# m_ch_ho_n_ch_nh.net
KiCad netlist of a schematic drawn in Altium Designer
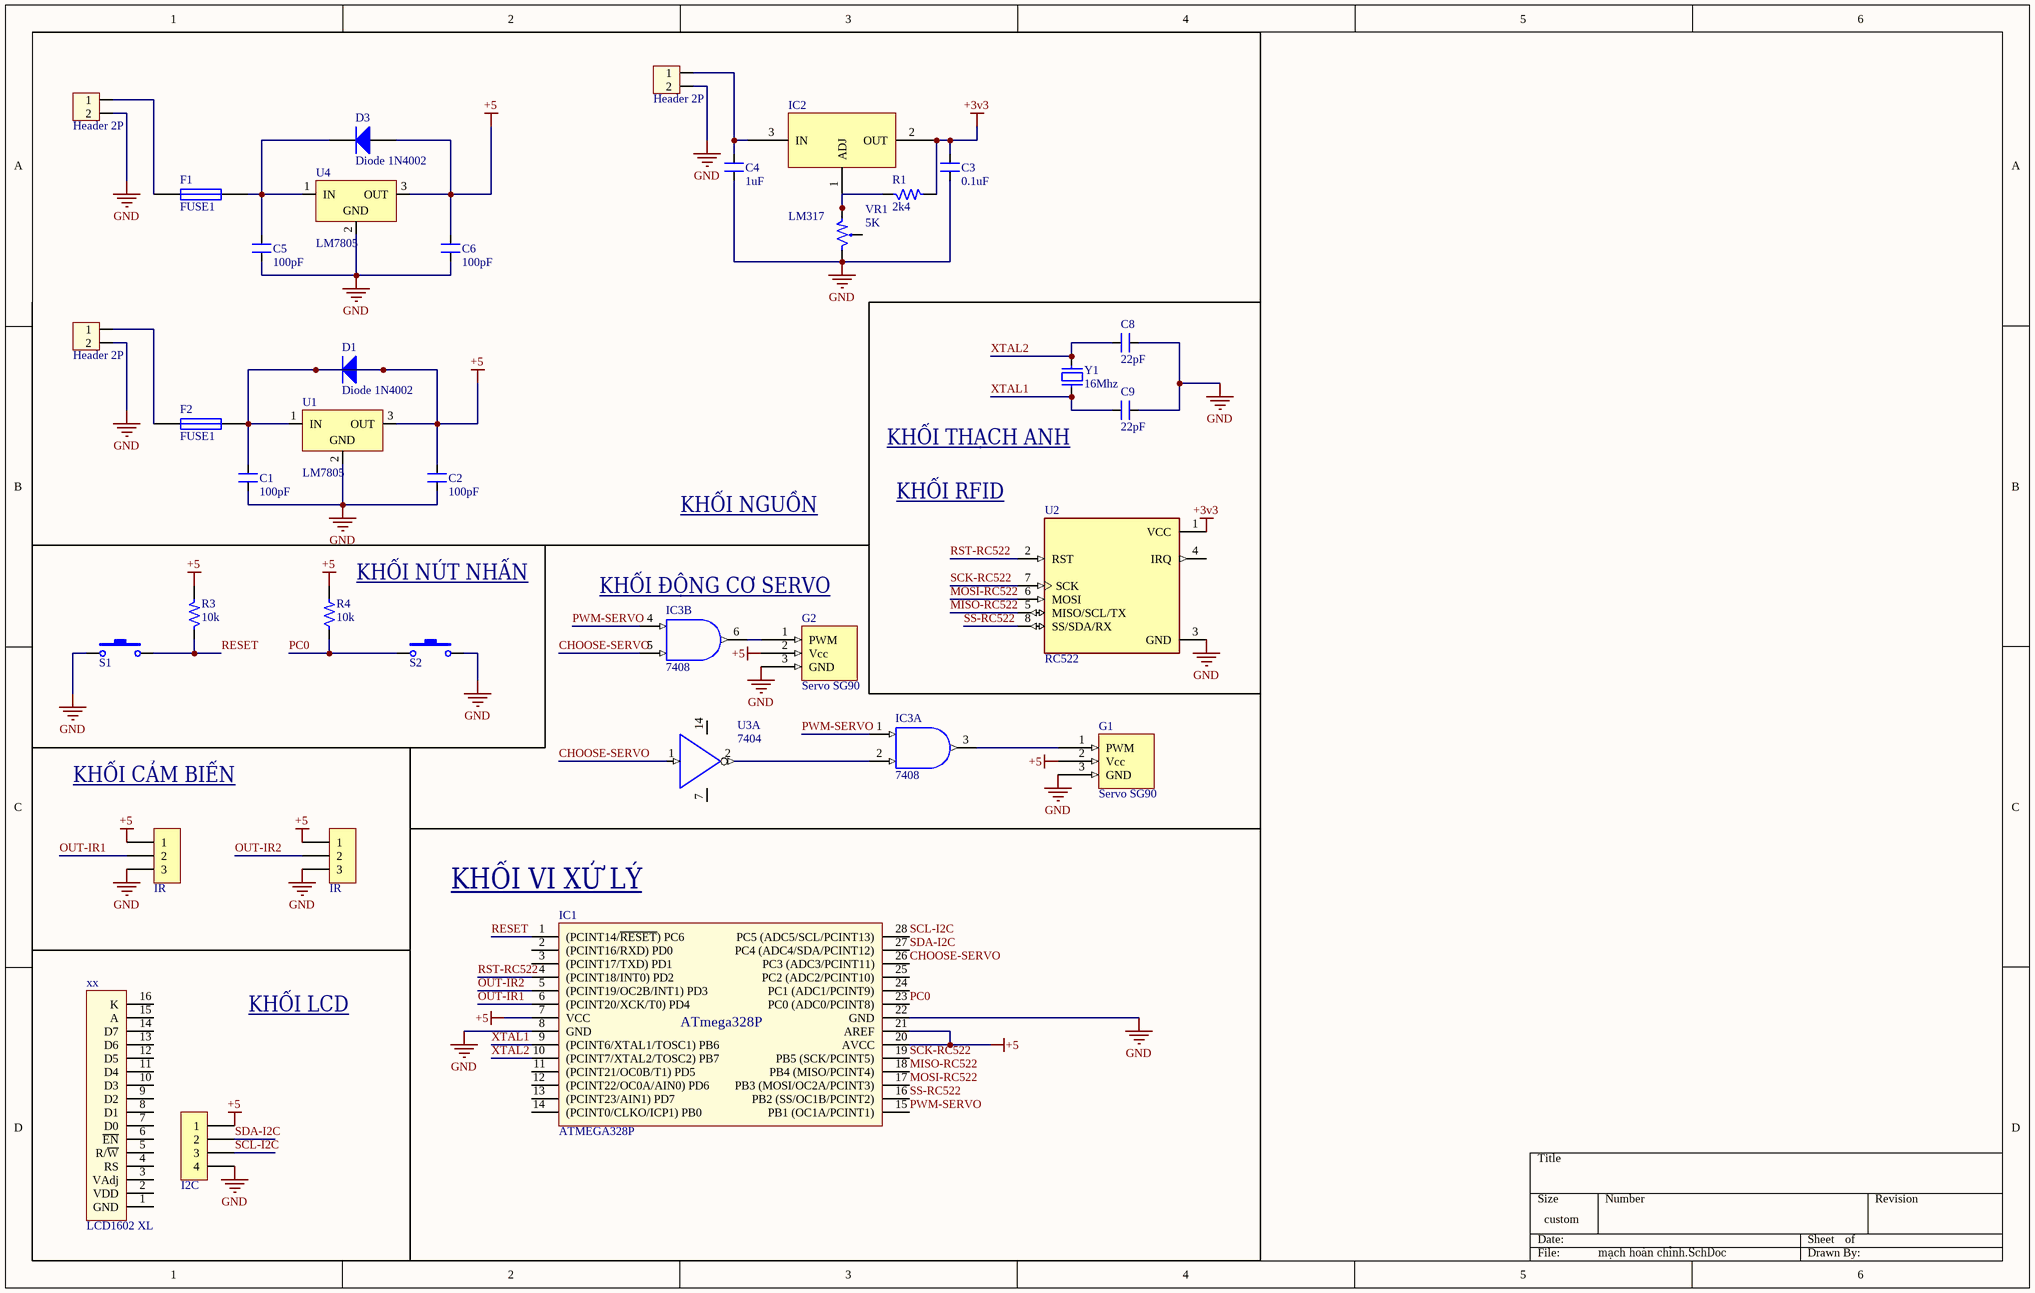
[diagram p0: mạch hoàn chỉnh.SchDoc]

(export (version "E")
  (design (tool "Eeschema 10.0.6"))
  (components
    (comp (ref "C1")
      (value "100pF")
      (footprint "CAP_100UF_50V")
      (description "Cap np  1pF - 472pF")
      (libsource (lib "lpson") (part "CN1"))
    )
    (comp (ref "C2")
      (value "100pF")
      (footprint "LPON_CAP:CAP_100UF_50V")
      (description "Cap np  1pF - 472pF")
      (libsource (lib "lpson") (part "CN1"))
    )
    (comp (ref "C3")
      (value "0.1uF")
      (footprint "Tu gom 104")
      (description "Cap np 104 => 105pF")
      (libsource (lib "lpson") (part "CN2"))
    )
    (comp (ref "C4")
      (value "1uF")
      (footprint "Tu gom 104")
      (description "Cap np  1pF - 472pF")
      (libsource (lib "lpson") (part "CN1"))
    )
    (comp (ref "C5")
      (value "100pF")
      (footprint "CAP_100UF_50V")
      (description "Cap np  1pF - 472pF")
      (libsource (lib "lpson") (part "CN1"))
    )
    (comp (ref "C6")
      (value "100pF")
      (footprint "LPON_CAP:CAP_100UF_50V")
      (description "Cap np  1pF - 472pF")
      (libsource (lib "lpson") (part "CN1"))
    )
    (comp (ref "C8")
      (value "22pF")
      (footprint "CAP_100UF_50V")
      (description "Cap np  1pF - 472pF")
      (libsource (lib "lpson") (part "CN1"))
    )
    (comp (ref "C9")
      (value "22pF")
      (footprint "CAP_100UF_50V")
      (description "Cap np  1pF - 472pF")
      (libsource (lib "lpson") (part "CN1"))
    )
    (comp (ref "D1")
      (value "Diode 1N4002")
      (footprint "LPSON_DIODE2:1N4007")
      (description "1 Amp General Purpose Rectifier")
      (fields (field (name "PUBLISHER") "Altium Limited"))
      (libsource (lib "lpson") (part "Diode 1N4002"))
    )
    (comp (ref "D3")
      (value "Diode 1N4002")
      (footprint "LPSON_DIODE2:1N4007")
      (description "1 Amp General Purpose Rectifier")
      (fields (field (name "PUBLISHER") "Altium Limited"))
      (libsource (lib "lpson") (part "Diode 1N4002"))
    )
    (comp (ref "F1") (value "FUSE1") (description "Fuse") (libsource (lib "Cty1") (part "FUSE1")))
    (comp (ref "F2") (value "FUSE1") (description "Fuse") (libsource (lib "Cty1") (part "FUSE1")))
    (comp (ref "G1")
      (value "Servo SG90")
      (footprint "Altium_Lib_by_KhueNguyenCreator:Header 3P DC 2.54")
      (description "180o")
      (libsource (lib "SG90") (part "Servo SG90"))
    )
    (comp (ref "G2")
      (value "Servo SG90")
      (footprint "Altium_Lib_by_KhueNguyenCreator:Header 3P DC 2.54")
      (description "180o")
      (libsource (lib "SG90") (part "Servo SG90"))
    )
    (comp (ref "H1")
      (value "Header 2P")
      (footprint "XH2.54M-2")
      (description "Cắm")
      (libsource (lib "Altium_Lib_by_KhueNguyenCreator") (part "Header 2P 2.54 Duc Thang"))
    )
    (comp (ref "H2")
      (value "I2C")
      (footprint "XH2.54M-4")
      (description "Cắm")
      (libsource (lib "Altium_Lib_by_KhueNguyenCreator") (part "Header 4P 2.54 Duc Thang"))
    )
    (comp (ref "H3")
      (value "IR")
      (footprint "VH3.96M-3")
      (description "Cắm")
      (libsource (lib "Altium_Lib_by_KhueNguyenCreator") (part "Header 3P VH3.96 Duc Thang"))
    )
    (comp (ref "H4")
      (value "IR")
      (footprint "VH3.96M-3")
      (description "Cắm")
      (libsource (lib "Altium_Lib_by_KhueNguyenCreator") (part "Header 3P VH3.96 Duc Thang"))
    )
    (comp (ref "H5")
      (value "Header 2P")
      (footprint "XH2.54M-2")
      (description "Cắm")
      (libsource (lib "Altium_Lib_by_KhueNguyenCreator") (part "Header 2P 2.54 Duc Thang"))
    )
    (comp (ref "H6")
      (value "Header 2P")
      (footprint "XH2.54M-2")
      (description "Cắm")
      (libsource (lib "Altium_Lib_by_KhueNguyenCreator") (part "Header 2P 2.54 Duc Thang"))
    )
    (comp (ref "IC1")
      (value "ATMEGA328P")
      (footprint "SOCKET_28")
      (description "Flash 32K, Bytes EEPROM 1K Bytes, RAM 2K Bytes")
      (libsource (lib "lpson") (part "ATmega328P"))
    )
    (comp (ref "IC2")
      (value "LM317")
      (footprint "TO220H1")
      (description "Cắm")
      (libsource (lib "Altium_Lib_by_KhueNguyenCreator") (part "LM317 TO220"))
    )
    (comp (ref "IC3")
      (value "7408")
      (footprint "DIP14")
      (description "Quad 2-Input AND Gate")
      (libsource (lib "Cty1") (part "7408"))
    )
    (comp (ref "R1")
      (value "2k4")
      (footprint "CFR25S")
      (description "Resistor 1/4W")
      (libsource (lib "lpson") (part "R"))
    )
    (comp (ref "R3")
      (value "10k")
      (footprint "CFR25S")
      (description "Resistor 1/4W")
      (libsource (lib "lpson") (part "R"))
    )
    (comp (ref "R4")
      (value "10k")
      (footprint "CFR25S")
      (description "Resistor 1/4W")
      (libsource (lib "lpson") (part "R"))
    )
    (comp (ref "S1")
      (value "EVQ11A04M")
      (footprint "LPON_OTHER:BUTTON 2 PIN")
      (description "Tact Switch 2 Pins White 6mm")
      (libsource (lib "lpson") (part "EVQ11A04M"))
    )
    (comp (ref "S2")
      (value "EVQ11A04M")
      (footprint "LPON_OTHER:BUTTON 2 PIN")
      (description "Tact Switch 2 Pins White 6mm")
      (libsource (lib "lpson") (part "EVQ11A04M"))
    )
    (comp (ref "U1")
      (value "LM7805")
      (footprint "LM7805")
      (description "Linear Voltage Regulator 5V 1A 24V Max TO-220")
      (libsource (lib "lpson") (part "LM7805"))
    )
    (comp (ref "U2")
      (value "RC522")
      (footprint "MODULE_CEG006900")
      (description "RFID RC522 Reader IC Card Module Tags SPI Interface Read and Write")
      (fields (field (name "MP") "CEG006900") (field (name "MF") "YKS"))
      (libsource (lib "CEG006900 (1)") (part "CEG006900"))
    )
    (comp (ref "U3") (value "7404") (footprint "DO14") (libsource (lib "Cty1") (part "7404")))
    (comp (ref "U4")
      (value "LM7805")
      (footprint "LM7805")
      (description "Linear Voltage Regulator 5V 1A 24V Max TO-220")
      (libsource (lib "lpson") (part "LM7805"))
    )
    (comp (ref "VR1")
      (value "5K")
      (footprint "VR1")
      (description "Var Resistor")
      (libsource (lib "lpson") (part "VR2"))
    )
    (comp (ref "xx")
      (value "LCD1602 XL")
      (footprint "LCD1602 with Jump")
      (description "LCD 1602 Xanh Lá")
      (libsource (lib "Altium_Lib_by_KhueNguyenCreator") (part "LCD1602 XL"))
    )
    (comp (ref "Y1")
      (value "16Mhz")
      (footprint "Thach Anh 2 chan cam")
      (description "Crystal For all Crystal 2pin.")
      (libsource (lib "Altium_Lib_by_KhueNguyenCreator") (part "Thach Anh 2 chan Cam"))
    )
  )
  (nets
    (net (code "1") (name "+3v3") (class "Default")
      (node (ref "C3") (pin "2") (pinfunction "2_2") (pintype "passive"))
      (node (ref "IC2") (pin "2") (pinfunction "OUT_2") (pintype "passive"))
      (node (ref "R1") (pin "2") (pinfunction "2_2") (pintype "passive"))
      (node (ref "U2") (pin "1") (pinfunction "VCC_1") (pintype "power_in"))
    )
    (net (code "2") (name "+5") (class "Default")
      (node (ref "C1") (pin "2") (pinfunction "2_2") (pintype "passive"))
      (node (ref "C2") (pin "2") (pinfunction "2_2") (pintype "passive"))
      (node (ref "C6") (pin "2") (pinfunction "2_2") (pintype "passive"))
      (node (ref "D1") (pin "1") (pinfunction "A_1") (pintype "passive"))
      (node (ref "D1") (pin "2") (pinfunction "K_2") (pintype "passive"))
      (node (ref "D3") (pin "1") (pinfunction "A_1") (pintype "passive"))
      (node (ref "F2") (pin "2") (pinfunction "2_2") (pintype "passive"))
      (node (ref "G1") (pin "2") (pinfunction "Vcc_2") (pintype "input"))
      (node (ref "G2") (pin "2") (pinfunction "Vcc_2") (pintype "input"))
      (node (ref "H2") (pin "1") (pinfunction "1_1") (pintype "passive"))
      (node (ref "H3") (pin "1") (pinfunction "1_1") (pintype "passive"))
      (node (ref "H4") (pin "1") (pinfunction "1_1") (pintype "passive"))
      (node (ref "IC1") (pin "20") (pinfunction "AVCC_20") (pintype "passive"))
      (node (ref "IC1") (pin "21") (pinfunction "AREF_21") (pintype "passive"))
      (node (ref "IC1") (pin "7") (pinfunction "VCC_7") (pintype "passive"))
      (node (ref "R3") (pin "2") (pinfunction "2_2") (pintype "passive"))
      (node (ref "R4") (pin "2") (pinfunction "2_2") (pintype "passive"))
      (node (ref "U1") (pin "1") (pinfunction "IN_1") (pintype "power_in"))
      (node (ref "U1") (pin "3") (pinfunction "OUT_3") (pintype "power_in"))
      (node (ref "U4") (pin "3") (pinfunction "OUT_3") (pintype "power_in"))
    )
    (net (code "3") (name "/CHOOSE-SERVO") (class "Default")
      (node (ref "IC1") (pin "26") (pinfunction "PC3_(ADC3/PCINT11)_26") (pintype "passive"))
      (node (ref "IC3") (pin "5") (pinfunction "B_5") (pintype "input"))
      (node (ref "U3") (pin "1") (pinfunction "A_1") (pintype "input"))
    )
    (net (code "4") (name "/MISO-RC522") (class "Default")
      (node (ref "IC1") (pin "18") (pinfunction "PB4_(MISO/PCINT4)_18") (pintype "passive"))
      (node (ref "U2") (pin "5") (pinfunction "MISO/SCL/TX_5") (pintype "bidirectional"))
    )
    (net (code "5") (name "/MOSI-RC522") (class "Default")
      (node (ref "IC1") (pin "17") (pinfunction "PB3_(MOSI/OC2A/PCINT3)_17") (pintype "passive"))
      (node (ref "U2") (pin "6") (pinfunction "MOSI_6") (pintype "input"))
    )
    (net (code "6") (name "/OUT-IR1") (class "Default")
      (node (ref "H3") (pin "2") (pinfunction "2_2") (pintype "passive"))
      (node (ref "IC1") (pin "6") (pinfunction "(PCINT20/XCK/T0)_PD4_6") (pintype "passive"))
    )
    (net (code "7") (name "/OUT-IR2") (class "Default")
      (node (ref "H4") (pin "2") (pinfunction "2_2") (pintype "passive"))
      (node (ref "IC1") (pin "5") (pinfunction "(PCINT19/OC2B/INT1)_PD3_5") (pintype "passive"))
    )
    (net (code "8") (name "/PC0") (class "Default")
      (node (ref "IC1") (pin "23") (pinfunction "PC0_(ADC0/PCINT8)_23") (pintype "passive"))
      (node (ref "R4") (pin "1") (pinfunction "1_1") (pintype "passive"))
      (node (ref "S2") (pin "2") (pinfunction "B_2") (pintype "passive"))
    )
    (net (code "9") (name "/PWM-SERVO") (class "Default")
      (node (ref "IC1") (pin "15") (pinfunction "PB1_(OC1A/PCINT1)_15") (pintype "passive"))
      (node (ref "IC3") (pin "1") (pinfunction "A_1") (pintype "input"))
      (node (ref "IC3") (pin "4") (pinfunction "A_4") (pintype "input"))
    )
    (net (code "10") (name "/RESET") (class "Default")
      (node (ref "IC1") (pin "1") (pinfunction "(PCINT14/~{RESET})_PC6_1") (pintype "passive"))
      (node (ref "R3") (pin "1") (pinfunction "1_1") (pintype "passive"))
      (node (ref "S1") (pin "2") (pinfunction "B_2") (pintype "passive"))
    )
    (net (code "11") (name "/RST-RC522") (class "Default")
      (node (ref "IC1") (pin "4") (pinfunction "(PCINT18/INT0)_PD2_4") (pintype "passive"))
      (node (ref "U2") (pin "2") (pinfunction "RST_2") (pintype "input"))
    )
    (net (code "12") (name "/SCK-RC522") (class "Default")
      (node (ref "IC1") (pin "19") (pinfunction "PB5_(SCK/PCINT5)_19") (pintype "passive"))
      (node (ref "U2") (pin "7") (pinfunction "SCK_7") (pintype "input"))
    )
    (net (code "13") (name "/SCL-I2C") (class "Default")
      (node (ref "H2") (pin "3") (pinfunction "3_3") (pintype "passive"))
      (node (ref "IC1") (pin "28") (pinfunction "PC5_(ADC5/SCL/PCINT13)_28") (pintype "passive"))
    )
    (net (code "14") (name "/SDA-I2C") (class "Default")
      (node (ref "H2") (pin "2") (pinfunction "2_2") (pintype "passive"))
      (node (ref "IC1") (pin "27") (pinfunction "PC4_(ADC4/SDA/PCINT12)_27") (pintype "passive"))
    )
    (net (code "15") (name "/SS-RC522") (class "Default")
      (node (ref "IC1") (pin "16") (pinfunction "PB2_(SS/OC1B/PCINT2)_16") (pintype "passive"))
      (node (ref "U2") (pin "8") (pinfunction "SS/SDA/RX_8") (pintype "bidirectional"))
    )
    (net (code "16") (name "/XTAL1") (class "Default")
      (node (ref "C9") (pin "2") (pinfunction "2_2") (pintype "passive"))
      (node (ref "IC1") (pin "9") (pinfunction "(PCINT6/XTAL1/TOSC1)_PB6_9") (pintype "passive"))
      (node (ref "Y1") (pin "1") (pinfunction "1_1") (pintype "passive"))
    )
    (net (code "17") (name "/XTAL2") (class "Default")
      (node (ref "C8") (pin "2") (pinfunction "2_2") (pintype "passive"))
      (node (ref "IC1") (pin "10") (pinfunction "(PCINT7/XTAL2/TOSC2)_PB7_10") (pintype "passive"))
      (node (ref "Y1") (pin "2") (pinfunction "2_2") (pintype "passive"))
    )
    (net (code "18") (name "GND") (class "Default")
      (node (ref "C1") (pin "1") (pinfunction "1_1") (pintype "passive"))
      (node (ref "C2") (pin "1") (pinfunction "1_1") (pintype "passive"))
      (node (ref "C3") (pin "1") (pinfunction "1_1") (pintype "passive"))
      (node (ref "C4") (pin "1") (pinfunction "1_1") (pintype "passive"))
      (node (ref "C5") (pin "1") (pinfunction "1_1") (pintype "passive"))
      (node (ref "C6") (pin "1") (pinfunction "1_1") (pintype "passive"))
      (node (ref "C8") (pin "1") (pinfunction "1_1") (pintype "passive"))
      (node (ref "C9") (pin "1") (pinfunction "1_1") (pintype "passive"))
      (node (ref "G1") (pin "3") (pinfunction "GND_3") (pintype "input"))
      (node (ref "G2") (pin "3") (pinfunction "GND_3") (pintype "input"))
      (node (ref "H1") (pin "2") (pinfunction "2_2") (pintype "passive"))
      (node (ref "H2") (pin "4") (pinfunction "4_4") (pintype "passive"))
      (node (ref "H3") (pin "3") (pinfunction "3_3") (pintype "passive"))
      (node (ref "H4") (pin "3") (pinfunction "3_3") (pintype "passive"))
      (node (ref "H5") (pin "2") (pinfunction "2_2") (pintype "passive"))
      (node (ref "H6") (pin "2") (pinfunction "2_2") (pintype "passive"))
      (node (ref "IC1") (pin "22") (pinfunction "GND_22") (pintype "passive"))
      (node (ref "IC1") (pin "8") (pinfunction "GND_8") (pintype "passive"))
      (node (ref "IC3") (pin "7") (pinfunction "GND_7") (pintype "power_in"))
      (node (ref "S1") (pin "1") (pinfunction "A_1") (pintype "passive"))
      (node (ref "S2") (pin "1") (pinfunction "A_1") (pintype "passive"))
      (node (ref "U1") (pin "2") (pinfunction "GND_2") (pintype "power_in"))
      (node (ref "U2") (pin "3") (pinfunction "GND_3") (pintype "power_in"))
      (node (ref "U4") (pin "2") (pinfunction "GND_2") (pintype "power_in"))
      (node (ref "VR1") (pin "3") (pinfunction "3_3") (pintype "passive"))
    )
    (net (code "19") (name "Net-(D3-K)") (class "Default")
      (node (ref "C5") (pin "2") (pinfunction "2_2") (pintype "passive"))
      (node (ref "D3") (pin "2") (pinfunction "K_2") (pintype "passive"))
      (node (ref "F1") (pin "2") (pinfunction "2_2") (pintype "passive"))
      (node (ref "U4") (pin "1") (pinfunction "IN_1") (pintype "power_in"))
    )
    (net (code "20") (name "Net-(F1-Pad1)") (class "Default")
      (node (ref "F1") (pin "1") (pinfunction "1_1") (pintype "passive"))
      (node (ref "H6") (pin "1") (pinfunction "1_1") (pintype "passive"))
    )
    (net (code "21") (name "Net-(F2-Pad1)") (class "Default")
      (node (ref "F2") (pin "1") (pinfunction "1_1") (pintype "passive"))
      (node (ref "H1") (pin "1") (pinfunction "1_1") (pintype "passive"))
    )
    (net (code "22") (name "Net-(G1-PWM)") (class "Default")
      (node (ref "G1") (pin "1") (pinfunction "PWM_1") (pintype "input"))
      (node (ref "IC3") (pin "3") (pinfunction "O_3") (pintype "output"))
    )
    (net (code "23") (name "Net-(G2-PWM)") (class "Default")
      (node (ref "G2") (pin "1") (pinfunction "PWM_1") (pintype "input"))
      (node (ref "IC3") (pin "6") (pinfunction "O_6") (pintype "output"))
    )
    (net (code "24") (name "Net-(IC2-ADJ)") (class "Default")
      (node (ref "IC2") (pin "1") (pinfunction "ADJ_1") (pintype "passive"))
      (node (ref "R1") (pin "1") (pinfunction "1_1") (pintype "passive"))
      (node (ref "VR1") (pin "1") (pinfunction "1_1") (pintype "passive"))
    )
    (net (code "25") (name "Net-(IC2-IN)") (class "Default")
      (node (ref "C4") (pin "2") (pinfunction "2_2") (pintype "passive"))
      (node (ref "H5") (pin "1") (pinfunction "1_1") (pintype "passive"))
      (node (ref "IC2") (pin "3") (pinfunction "IN_3") (pintype "passive"))
    )
    (net (code "26") (name "Net-(IC3A-B)") (class "Default")
      (node (ref "IC3") (pin "2") (pinfunction "B_2") (pintype "input"))
      (node (ref "U3") (pin "2") (pinfunction "Y_2") (pintype "output"))
    )
    (net (code "27") (name "VCC") (class "Default")
      (node (ref "IC3") (pin "14") (pinfunction "VCC_14") (pintype "power_in"))
    )
    (net (code "28") (name "unconnected-(IC1-(PCINT0{slash}CLKO{slash}ICP1)_PB0-Pad14)") (class "Default")
      (node (ref "IC1") (pin "14") (pinfunction "(PCINT0/CLKO/ICP1)_PB0_14") (pintype "passive"))
    )
    (net (code "29") (name "unconnected-(IC1-(PCINT16{slash}RXD)_PD0-Pad2)") (class "Default")
      (node (ref "IC1") (pin "2") (pinfunction "(PCINT16/RXD)_PD0_2") (pintype "passive"))
    )
    (net (code "30") (name "unconnected-(IC1-(PCINT17{slash}TXD)_PD1-Pad3)") (class "Default")
      (node (ref "IC1") (pin "3") (pinfunction "(PCINT17/TXD)_PD1_3") (pintype "passive"))
    )
    (net (code "31") (name "unconnected-(IC1-(PCINT21{slash}OC0B{slash}T1)_PD5-Pad11)") (class "Default")
      (node (ref "IC1") (pin "11") (pinfunction "(PCINT21/OC0B/T1)_PD5_11") (pintype "passive"))
    )
    (net (code "32") (name "unconnected-(IC1-(PCINT22{slash}OC0A{slash}AIN0)_PD6-Pad12)") (class "Default")
      (node (ref "IC1") (pin "12") (pinfunction "(PCINT22/OC0A/AIN0)_PD6_12") (pintype "passive"))
    )
    (net (code "33") (name "unconnected-(IC1-(PCINT23{slash}AIN1)_PD7-Pad13)") (class "Default")
      (node (ref "IC1") (pin "13") (pinfunction "(PCINT23/AIN1)_PD7_13") (pintype "passive"))
    )
    (net (code "34") (name "unconnected-(IC1-PC1_(ADC1{slash}PCINT9)-Pad24)") (class "Default")
      (node (ref "IC1") (pin "24") (pinfunction "PC1_(ADC1/PCINT9)_24") (pintype "passive"))
    )
    (net (code "35") (name "unconnected-(IC1-PC2_(ADC2{slash}PCINT10)-Pad25)") (class "Default")
      (node (ref "IC1") (pin "25") (pinfunction "PC2_(ADC2/PCINT10)_25") (pintype "passive"))
    )
    (net (code "36") (name "unconnected-(U2-IRQ-Pad4)") (class "Default")
      (node (ref "U2") (pin "4") (pinfunction "IRQ_4") (pintype "output"))
    )
    (net (code "37") (name "unconnected-(U3A-GND-Pad7)") (class "Default")
      (node (ref "U3") (pin "7") (pinfunction "GND_7") (pintype "power_in"))
    )
    (net (code "38") (name "unconnected-(U3A-VCC-Pad14)") (class "Default")
      (node (ref "U3") (pin "14") (pinfunction "VCC_14") (pintype "power_in"))
    )
    (net (code "39") (name "unconnected-(VR1-Pad2)") (class "Default")
      (node (ref "VR1") (pin "2") (pinfunction "2_2") (pintype "passive"))
    )
    (net (code "40") (name "unconnected-(xx-A-Pad15)") (class "Default")
      (node (ref "xx") (pin "15") (pinfunction "A_15") (pintype "passive"))
    )
    (net (code "41") (name "unconnected-(xx-D0-Pad7)") (class "Default")
      (node (ref "xx") (pin "7") (pinfunction "D0_7") (pintype "passive"))
    )
    (net (code "42") (name "unconnected-(xx-D1-Pad8)") (class "Default")
      (node (ref "xx") (pin "8") (pinfunction "D1_8") (pintype "passive"))
    )
    (net (code "43") (name "unconnected-(xx-D2-Pad9)") (class "Default")
      (node (ref "xx") (pin "9") (pinfunction "D2_9") (pintype "passive"))
    )
    (net (code "44") (name "unconnected-(xx-D3-Pad10)") (class "Default")
      (node (ref "xx") (pin "10") (pinfunction "D3_10") (pintype "passive"))
    )
    (net (code "45") (name "unconnected-(xx-D4-Pad11)") (class "Default")
      (node (ref "xx") (pin "11") (pinfunction "D4_11") (pintype "passive"))
    )
    (net (code "46") (name "unconnected-(xx-D5-Pad12)") (class "Default")
      (node (ref "xx") (pin "12") (pinfunction "D5_12") (pintype "passive"))
    )
    (net (code "47") (name "unconnected-(xx-D6-Pad13)") (class "Default")
      (node (ref "xx") (pin "13") (pinfunction "D6_13") (pintype "passive"))
    )
    (net (code "48") (name "unconnected-(xx-D7-Pad14)") (class "Default")
      (node (ref "xx") (pin "14") (pinfunction "D7_14") (pintype "passive"))
    )
    (net (code "49") (name "unconnected-(xx-GND-Pad1)") (class "Default")
      (node (ref "xx") (pin "1") (pinfunction "GND_1") (pintype "passive"))
    )
    (net (code "50") (name "unconnected-(xx-K-Pad16)") (class "Default")
      (node (ref "xx") (pin "16") (pinfunction "K_16") (pintype "passive"))
    )
    (net (code "51") (name "unconnected-(xx-RS-Pad4)") (class "Default")
      (node (ref "xx") (pin "4") (pinfunction "RS_4") (pintype "passive"))
    )
    (net (code "52") (name "unconnected-(xx-R{slash}~{W}-Pad5)") (class "Default")
      (node (ref "xx") (pin "5") (pinfunction "R/~{W}_5") (pintype "passive"))
    )
    (net (code "53") (name "unconnected-(xx-VAdj-Pad3)") (class "Default")
      (node (ref "xx") (pin "3") (pinfunction "VAdj_3") (pintype "passive"))
    )
    (net (code "54") (name "unconnected-(xx-VDD-Pad2)") (class "Default")
      (node (ref "xx") (pin "2") (pinfunction "VDD_2") (pintype "passive"))
    )
    (net (code "55") (name "unconnected-(xx-~{EN}-Pad6)") (class "Default")
      (node (ref "xx") (pin "6") (pinfunction "~{EN}_6") (pintype "passive"))
    )
  )
)
